# voltage_regulator.net
KiCad netlist of a schematic drawn in EAGLE
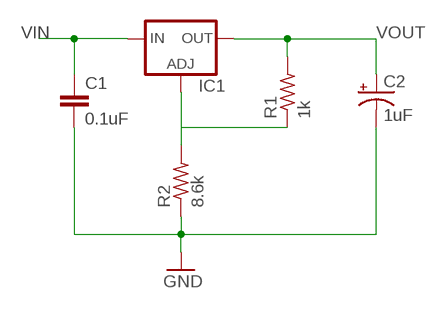
[diagram p0: schematic, sheet 1]

(export (version "E")
  (design (tool "Eeschema 10.0.6"))
  (components
    (comp (ref "C1")
      (value "0.1uF")
      (footprint "eagle-import:C2.5-3")
      (libsource (lib "eagle-import") (part "C2,5-3"))
    )
    (comp (ref "C2")
      (value "1uF")
      (footprint "eagle-import:153CLV-0810")
      (libsource (lib "eagle-import") (part "CPOL-US153CLV-0810"))
    )
    (comp (ref "IC1")
      (value "LM317TL")
      (footprint "eagle-import:317TL")
      (libsource (lib "eagle-import") (part "LM317TL"))
    )
    (comp (ref "R1")
      (value "1k")
      (footprint "eagle-import:0204_7")
      (libsource (lib "eagle-import") (part "R-US_0204/7"))
    )
    (comp (ref "R2")
      (value "8.6k")
      (footprint "eagle-import:0204_7")
      (libsource (lib "eagle-import") (part "R-US_0204/7"))
    )
  )
  (nets
    (net (code "1") (name "/VIN") (class "Default")
      (node (ref "C1") (pin "1") (pinfunction "1_1") (pintype "passive"))
      (node (ref "IC1") (pin "3") (pinfunction "IN_3") (pintype "input"))
    )
    (net (code "2") (name "/VOUT") (class "Default")
      (node (ref "C2") (pin "+") (pinfunction "+_+") (pintype "passive"))
      (node (ref "IC1") (pin "2") (pinfunction "OUT_2") (pintype "passive"))
      (node (ref "R1") (pin "2") (pinfunction "2_2") (pintype "passive"))
    )
    (net (code "3") (name "GND") (class "Default")
      (node (ref "C1") (pin "2") (pinfunction "2_2") (pintype "passive"))
      (node (ref "C2") (pin "-") (pinfunction "-_-") (pintype "passive"))
      (node (ref "R2") (pin "1") (pinfunction "1_1") (pintype "passive"))
    )
    (net (code "4") (name "Net-(IC1-ADJ)") (class "Default")
      (node (ref "IC1") (pin "1") (pinfunction "ADJ_1") (pintype "input"))
      (node (ref "R1") (pin "1") (pinfunction "1_1") (pintype "passive"))
      (node (ref "R2") (pin "2") (pinfunction "2_2") (pintype "passive"))
    )
  )
)
